# RSSI_Tag_V1.net
KiCad netlist of a schematic drawn in Altium Designer
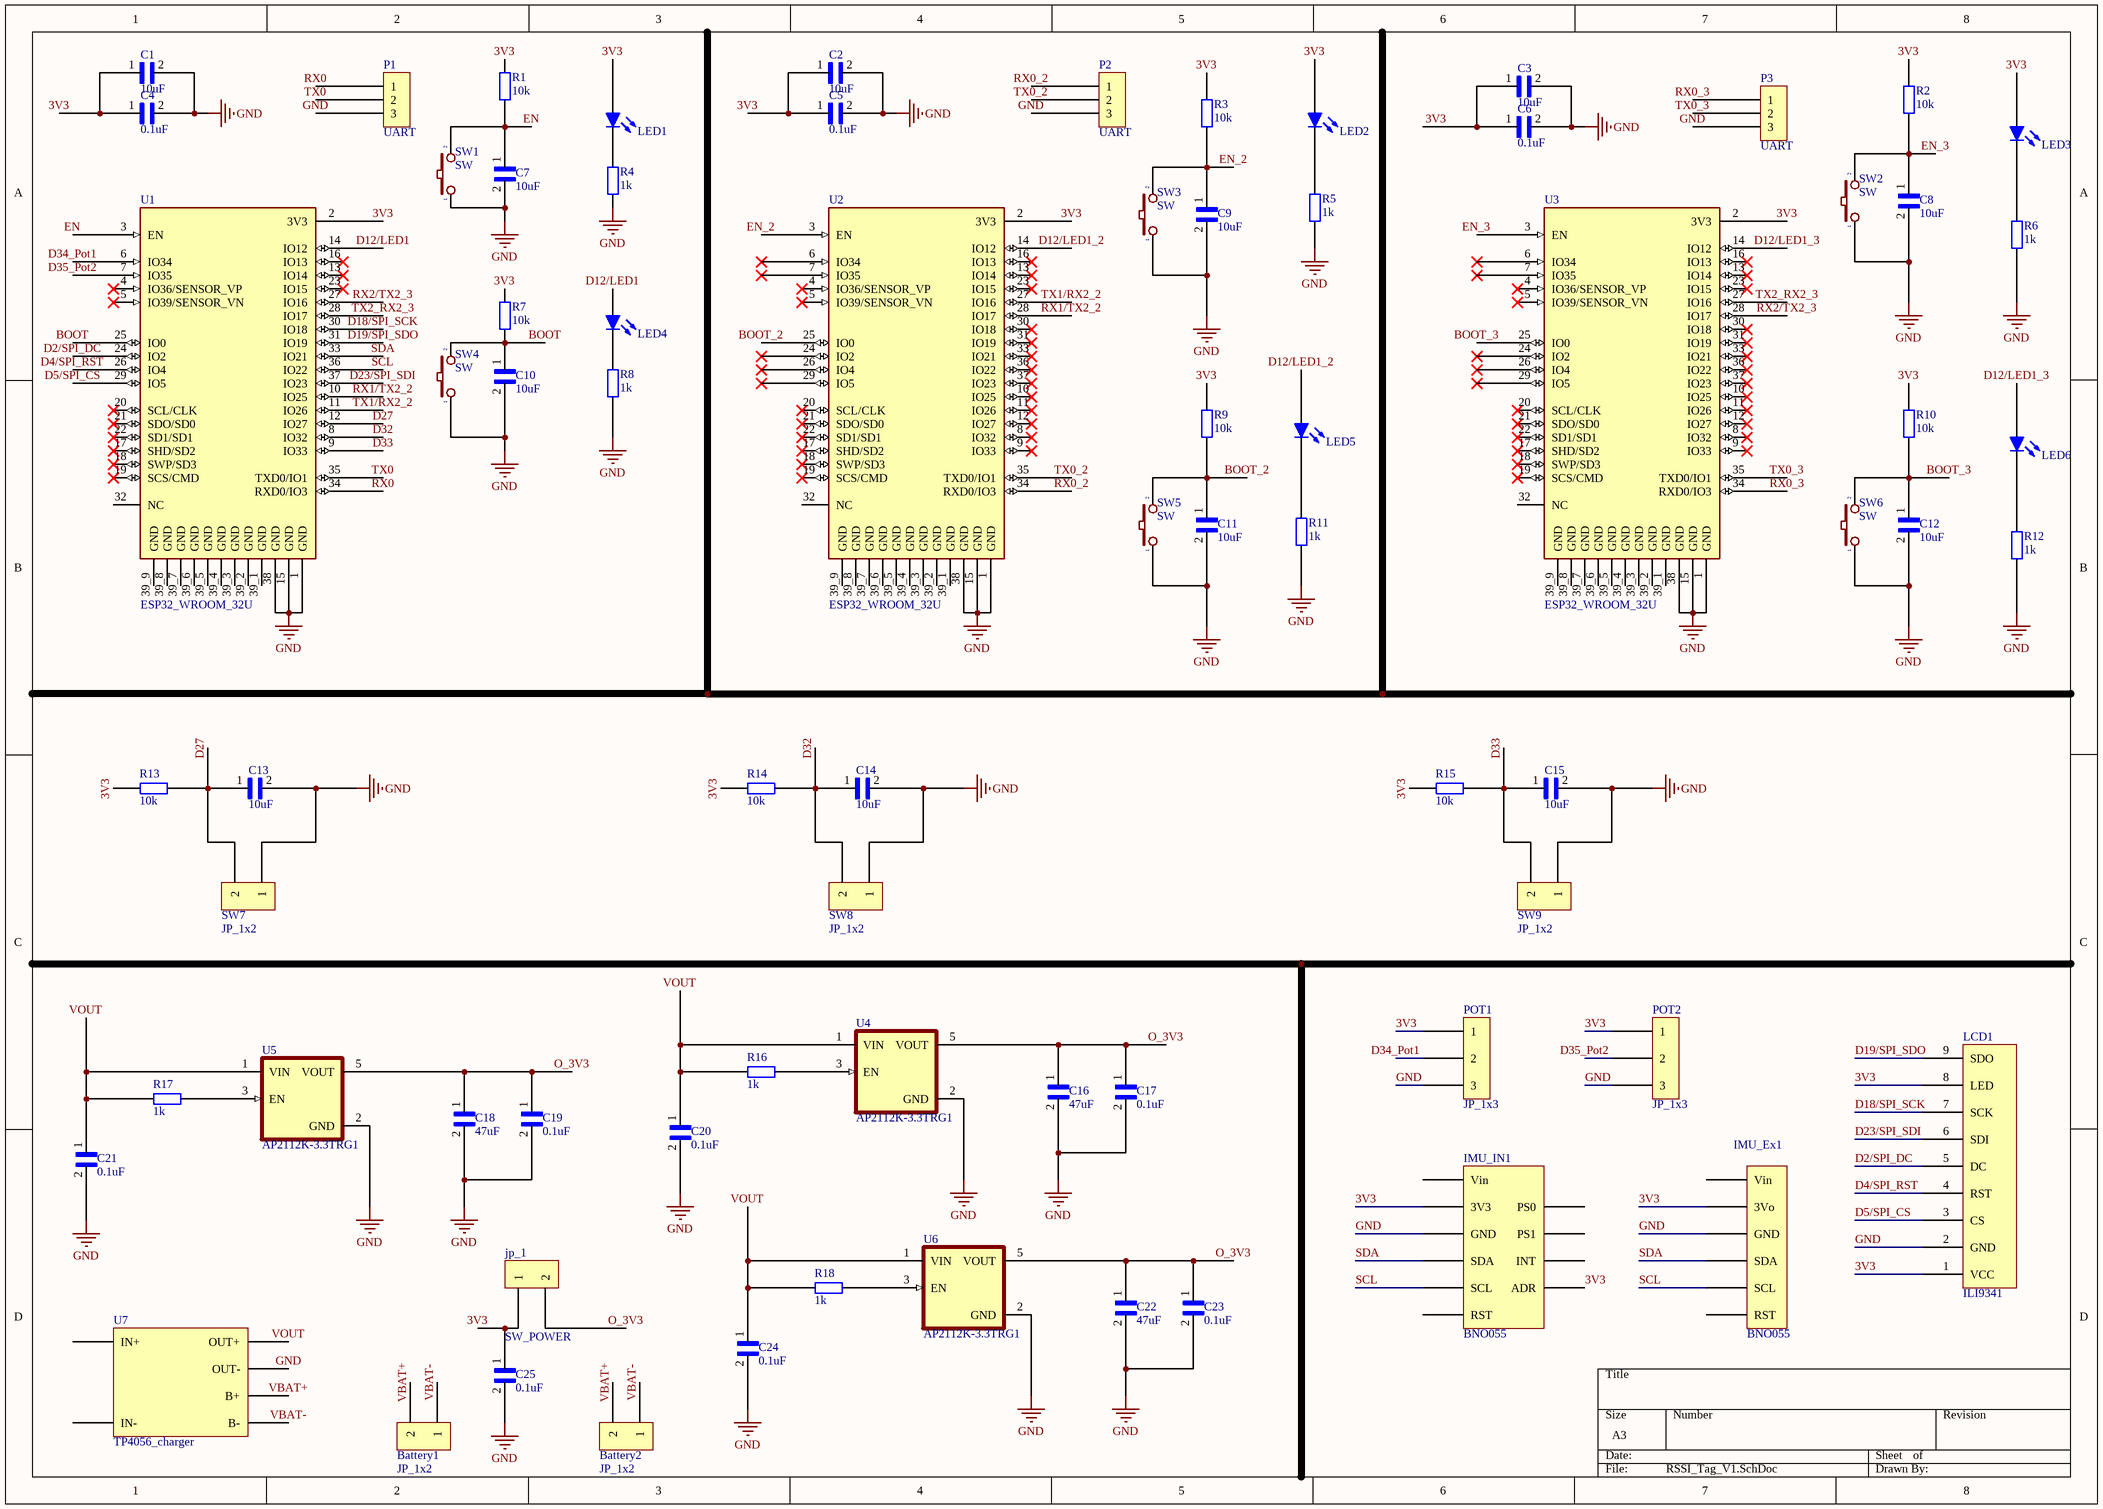
[diagram p0: RSSI_Tag_V1.SchDoc]

(export (version "E")
  (design (tool "Eeschema 10.0.6"))
  (components
    (comp (ref "Battery1")
      (value "JP_1x2")
      (footprint "JP_1x2")
      (libsource (lib "Target_tracking_20242v2") (part "JP_1x2"))
    )
    (comp (ref "Battery2")
      (value "JP_1x2")
      (footprint "JP_1x2")
      (libsource (lib "Target_tracking_20242v2") (part "JP_1x2"))
    )
    (comp (ref "C1")
      (value "10uF")
      (footprint "Capacitor_0805")
      (description "Capacitor; Ceramic; Cap; .220uF; Tol 10%; SMT; Vol-Rtg 50V; X7R; Tape And Reel")
      (libsource (lib "Target_tracking_20242v3") (part "Capacitor_0805"))
    )
    (comp (ref "C2")
      (value "10uF")
      (footprint "Capacitor_0805")
      (description "Capacitor; Ceramic; Cap; .220uF; Tol 10%; SMT; Vol-Rtg 50V; X7R; Tape And Reel")
      (libsource (lib "Target_tracking_20242v3") (part "Capacitor_0805"))
    )
    (comp (ref "C3")
      (value "10uF")
      (footprint "Capacitor_0805")
      (description "Capacitor; Ceramic; Cap; .220uF; Tol 10%; SMT; Vol-Rtg 50V; X7R; Tape And Reel")
      (libsource (lib "Target_tracking_20242v3") (part "Capacitor_0805"))
    )
    (comp (ref "C4")
      (value "0.1uF")
      (footprint "Capacitor_0805")
      (description "Capacitor; Ceramic; Cap; .220uF; Tol 10%; SMT; Vol-Rtg 50V; X7R; Tape And Reel")
      (libsource (lib "Target_tracking_20242v3") (part "Capacitor_0805"))
    )
    (comp (ref "C5")
      (value "0.1uF")
      (footprint "Capacitor_0805")
      (description "Capacitor; Ceramic; Cap; .220uF; Tol 10%; SMT; Vol-Rtg 50V; X7R; Tape And Reel")
      (libsource (lib "Target_tracking_20242v3") (part "Capacitor_0805"))
    )
    (comp (ref "C6")
      (value "0.1uF")
      (footprint "Capacitor_0805")
      (description "Capacitor; Ceramic; Cap; .220uF; Tol 10%; SMT; Vol-Rtg 50V; X7R; Tape And Reel")
      (libsource (lib "Target_tracking_20242v3") (part "Capacitor_0805"))
    )
    (comp (ref "C7")
      (value "10uF")
      (footprint "Capacitor_0805")
      (description "Capacitor; Ceramic; Cap; .220uF; Tol 10%; SMT; Vol-Rtg 50V; X7R; Tape And Reel")
      (libsource (lib "") (part "Capacitor_0805_1"))
    )
    (comp (ref "C8")
      (value "10uF")
      (footprint "Capacitor_0805")
      (description "Capacitor; Ceramic; Cap; .220uF; Tol 10%; SMT; Vol-Rtg 50V; X7R; Tape And Reel")
      (libsource (lib "") (part "Capacitor_0805_1"))
    )
    (comp (ref "C9")
      (value "10uF")
      (footprint "Capacitor_0805")
      (description "Capacitor; Ceramic; Cap; .220uF; Tol 10%; SMT; Vol-Rtg 50V; X7R; Tape And Reel")
      (libsource (lib "") (part "Capacitor_0805_1"))
    )
    (comp (ref "C10")
      (value "10uF")
      (footprint "Capacitor_0805")
      (description "Capacitor; Ceramic; Cap; .220uF; Tol 10%; SMT; Vol-Rtg 50V; X7R; Tape And Reel")
      (libsource (lib "") (part "Capacitor_0805_1"))
    )
    (comp (ref "C11")
      (value "10uF")
      (footprint "Capacitor_0805")
      (description "Capacitor; Ceramic; Cap; .220uF; Tol 10%; SMT; Vol-Rtg 50V; X7R; Tape And Reel")
      (libsource (lib "") (part "Capacitor_0805_1"))
    )
    (comp (ref "C12")
      (value "10uF")
      (footprint "Capacitor_0805")
      (description "Capacitor; Ceramic; Cap; .220uF; Tol 10%; SMT; Vol-Rtg 50V; X7R; Tape And Reel")
      (libsource (lib "") (part "Capacitor_0805_1"))
    )
    (comp (ref "C13")
      (value "10uF")
      (footprint "Capacitor_0805")
      (description "Capacitor; Ceramic; Cap; .220uF; Tol 10%; SMT; Vol-Rtg 50V; X7R; Tape And Reel")
      (libsource (lib "Target_tracking_20242v3") (part "Capacitor_0805"))
    )
    (comp (ref "C14")
      (value "10uF")
      (footprint "Capacitor_0805")
      (description "Capacitor; Ceramic; Cap; .220uF; Tol 10%; SMT; Vol-Rtg 50V; X7R; Tape And Reel")
      (libsource (lib "Target_tracking_20242v3") (part "Capacitor_0805"))
    )
    (comp (ref "C15")
      (value "10uF")
      (footprint "Capacitor_0805")
      (description "Capacitor; Ceramic; Cap; .220uF; Tol 10%; SMT; Vol-Rtg 50V; X7R; Tape And Reel")
      (libsource (lib "Target_tracking_20242v3") (part "Capacitor_0805"))
    )
    (comp (ref "C16")
      (value "47uF")
      (footprint "Capacitor_0805")
      (description "Capacitor; Ceramic; Cap; .220uF; Tol 10%; SMT; Vol-Rtg 50V; X7R; Tape And Reel")
      (libsource (lib "") (part "Capacitor_0805_1"))
    )
    (comp (ref "C17")
      (value "0.1uF")
      (footprint "Capacitor_0805")
      (description "Capacitor; Ceramic; Cap; .220uF; Tol 10%; SMT; Vol-Rtg 50V; X7R; Tape And Reel")
      (libsource (lib "") (part "Capacitor_0805_1"))
    )
    (comp (ref "C18")
      (value "47uF")
      (footprint "Capacitor_0805")
      (description "Capacitor; Ceramic; Cap; .220uF; Tol 10%; SMT; Vol-Rtg 50V; X7R; Tape And Reel")
      (libsource (lib "") (part "Capacitor_0805_1"))
    )
    (comp (ref "C19")
      (value "0.1uF")
      (footprint "Capacitor_0805")
      (description "Capacitor; Ceramic; Cap; .220uF; Tol 10%; SMT; Vol-Rtg 50V; X7R; Tape And Reel")
      (libsource (lib "") (part "Capacitor_0805_1"))
    )
    (comp (ref "C20")
      (value "0.1uF")
      (footprint "Capacitor_0805")
      (description "Capacitor; Ceramic; Cap; .220uF; Tol 10%; SMT; Vol-Rtg 50V; X7R; Tape And Reel")
      (libsource (lib "") (part "Capacitor_0805_1"))
    )
    (comp (ref "C21")
      (value "0.1uF")
      (footprint "Capacitor_0805")
      (description "Capacitor; Ceramic; Cap; .220uF; Tol 10%; SMT; Vol-Rtg 50V; X7R; Tape And Reel")
      (libsource (lib "") (part "Capacitor_0805_1"))
    )
    (comp (ref "C22")
      (value "47uF")
      (footprint "Capacitor_0805")
      (description "Capacitor; Ceramic; Cap; .220uF; Tol 10%; SMT; Vol-Rtg 50V; X7R; Tape And Reel")
      (libsource (lib "") (part "Capacitor_0805_1"))
    )
    (comp (ref "C23")
      (value "0.1uF")
      (footprint "Capacitor_0805")
      (description "Capacitor; Ceramic; Cap; .220uF; Tol 10%; SMT; Vol-Rtg 50V; X7R; Tape And Reel")
      (libsource (lib "") (part "Capacitor_0805_1"))
    )
    (comp (ref "C24")
      (value "0.1uF")
      (footprint "Capacitor_0805")
      (description "Capacitor; Ceramic; Cap; .220uF; Tol 10%; SMT; Vol-Rtg 50V; X7R; Tape And Reel")
      (libsource (lib "") (part "Capacitor_0805_1"))
    )
    (comp (ref "C25")
      (value "0.1uF")
      (footprint "Capacitor_0805")
      (description "Capacitor; Ceramic; Cap; .220uF; Tol 10%; SMT; Vol-Rtg 50V; X7R; Tape And Reel")
      (libsource (lib "") (part "Capacitor_0805_1"))
    )
    (comp (ref "IMU_Ex1")
      (value "BNO055")
      (footprint "BNO055_External")
      (libsource (lib "Target_tracking_20242v2") (part "BNO055_External"))
    )
    (comp (ref "IMU_IN1")
      (value "BNO055")
      (footprint "BNO055_Internal")
      (libsource (lib "Target_tracking_20242v3") (part "BNO055"))
    )
    (comp (ref "jp_1")
      (value "SW_POWER")
      (footprint "JP_1x2")
      (libsource (lib "Target_tracking_20242v3") (part "JP_1x2"))
    )
    (comp (ref "LCD1")
      (value "ILI9341")
      (footprint "ILI9341_LCD3.5")
      (libsource (lib "Target_tracking_20242v2") (part "ILI9341_LCD3.5"))
    )
    (comp (ref "LED1")
      (value "Led")
      (footprint "Led 0805 Blue")
      (description "Typical LED")
      (libsource (lib "Project_LoRa") (part "Led"))
    )
    (comp (ref "LED2")
      (value "Led")
      (footprint "Led 0805 Blue")
      (description "Typical LED")
      (libsource (lib "Project_LoRa") (part "Led"))
    )
    (comp (ref "LED3")
      (value "Led")
      (footprint "Led 0805 Blue")
      (description "Typical LED")
      (libsource (lib "Project_LoRa") (part "Led"))
    )
    (comp (ref "LED4")
      (value "Led")
      (footprint "Led 0805 Blue")
      (description "Typical LED")
      (libsource (lib "Project_LoRa") (part "Led"))
    )
    (comp (ref "LED5")
      (value "Led")
      (footprint "Led 0805 Blue")
      (description "Typical LED")
      (libsource (lib "Project_LoRa") (part "Led"))
    )
    (comp (ref "LED6")
      (value "Led")
      (footprint "Led 0805 Blue")
      (description "Typical LED")
      (libsource (lib "Project_LoRa") (part "Led"))
    )
    (comp (ref "P1")
      (value "UART")
      (footprint "HDR/Header/3/BOX")
      (description "Header, 3-Pin")
      (libsource (lib "Project_LoRa") (part "Header 3"))
    )
    (comp (ref "P2")
      (value "UART")
      (footprint "HDR/Header/3/BOX")
      (description "Header, 3-Pin")
      (libsource (lib "Project_LoRa") (part "Header 3"))
    )
    (comp (ref "P3")
      (value "UART")
      (footprint "HDR/Header/3/BOX")
      (description "Header, 3-Pin")
      (libsource (lib "Project_LoRa") (part "Header 3"))
    )
    (comp (ref "POT1")
      (value "JP_1x3")
      (footprint "JP_1x3")
      (libsource (lib "Target_tracking_20242v2") (part "JP_1x3"))
    )
    (comp (ref "POT2")
      (value "JP_1x3")
      (footprint "JP_1x3")
      (libsource (lib "Target_tracking_20242v2") (part "JP_1x3"))
    )
    (comp (ref "R1")
      (value "10k")
      (footprint "tro smd 0805")
      (description "Dán")
      (libsource (lib "Project_LoRa") (part "Tro 0805 1% 10k"))
    )
    (comp (ref "R2")
      (value "10k")
      (footprint "tro smd 0805")
      (description "Dán")
      (libsource (lib "Project_LoRa") (part "Tro 0805 1% 10k"))
    )
    (comp (ref "R3")
      (value "10k")
      (footprint "tro smd 0805")
      (description "Dán")
      (libsource (lib "Project_LoRa") (part "Tro 0805 1% 10k"))
    )
    (comp (ref "R4")
      (value "1k")
      (footprint "tro smd 0805")
      (description "Dán")
      (libsource (lib "Project_LoRa") (part "Tro 0805 1% 1k"))
    )
    (comp (ref "R5")
      (value "1k")
      (footprint "tro smd 0805")
      (description "Dán")
      (libsource (lib "Project_LoRa") (part "Tro 0805 1% 1k"))
    )
    (comp (ref "R6")
      (value "1k")
      (footprint "tro smd 0805")
      (description "Dán")
      (libsource (lib "Project_LoRa") (part "Tro 0805 1% 1k"))
    )
    (comp (ref "R7")
      (value "10k")
      (footprint "tro smd 0805")
      (description "Dán")
      (libsource (lib "Project_LoRa") (part "Tro 0805 1% 10k"))
    )
    (comp (ref "R8")
      (value "1k")
      (footprint "tro smd 0805")
      (description "Dán")
      (libsource (lib "Project_LoRa") (part "Tro 0805 1% 1k"))
    )
    (comp (ref "R9")
      (value "10k")
      (footprint "tro smd 0805")
      (description "Dán")
      (libsource (lib "Project_LoRa") (part "Tro 0805 1% 10k"))
    )
    (comp (ref "R10")
      (value "10k")
      (footprint "tro smd 0805")
      (description "Dán")
      (libsource (lib "Project_LoRa") (part "Tro 0805 1% 10k"))
    )
    (comp (ref "R11")
      (value "1k")
      (footprint "tro smd 0805")
      (description "Dán")
      (libsource (lib "Project_LoRa") (part "Tro 0805 1% 1k"))
    )
    (comp (ref "R12")
      (value "1k")
      (footprint "tro smd 0805")
      (description "Dán")
      (libsource (lib "Project_LoRa") (part "Tro 0805 1% 1k"))
    )
    (comp (ref "R13")
      (value "10k")
      (footprint "tro smd 0805")
      (description "Dán")
      (libsource (lib "Project_LoRa") (part "Tro 0805 1% 10k"))
    )
    (comp (ref "R14")
      (value "10k")
      (footprint "tro smd 0805")
      (description "Dán")
      (libsource (lib "Project_LoRa") (part "Tro 0805 1% 10k"))
    )
    (comp (ref "R15")
      (value "10k")
      (footprint "tro smd 0805")
      (description "Dán")
      (libsource (lib "Project_LoRa") (part "Tro 0805 1% 10k"))
    )
    (comp (ref "R16")
      (value "1k")
      (footprint "tro smd 0805")
      (description "Dán")
      (libsource (lib "Project_LoRa") (part "Tro 0805 1% 1k"))
    )
    (comp (ref "R17")
      (value "1k")
      (footprint "tro smd 0805")
      (description "Dán")
      (libsource (lib "Project_LoRa") (part "Tro 0805 1% 1k"))
    )
    (comp (ref "R18")
      (value "1k")
      (footprint "tro smd 0805")
      (description "Dán")
      (libsource (lib "Project_LoRa") (part "Tro 0805 1% 1k"))
    )
    (comp (ref "SW1")
      (value "SW")
      (footprint "SW1-SMD")
      (description "Switch button 2 pin")
      (libsource (lib "Project_LoRa") (part "SW2"))
    )
    (comp (ref "SW2")
      (value "SW")
      (footprint "SW1-SMD")
      (description "Switch button 2 pin")
      (libsource (lib "Project_LoRa") (part "SW2"))
    )
    (comp (ref "SW3")
      (value "SW")
      (footprint "SW1-SMD")
      (description "Switch button 2 pin")
      (libsource (lib "Project_LoRa") (part "SW2"))
    )
    (comp (ref "SW4")
      (value "SW")
      (footprint "SW1-SMD")
      (description "Switch button 2 pin")
      (libsource (lib "Project_LoRa") (part "SW2"))
    )
    (comp (ref "SW5")
      (value "SW")
      (footprint "SW1-SMD")
      (description "Switch button 2 pin")
      (libsource (lib "Project_LoRa") (part "SW2"))
    )
    (comp (ref "SW6")
      (value "SW")
      (footprint "SW1-SMD")
      (description "Switch button 2 pin")
      (libsource (lib "Project_LoRa") (part "SW2"))
    )
    (comp (ref "SW7")
      (value "JP_1x2")
      (footprint "JP_1x2")
      (libsource (lib "Target_tracking_20242v2") (part "JP_1x2"))
    )
    (comp (ref "SW8")
      (value "JP_1x2")
      (footprint "JP_1x2")
      (libsource (lib "Target_tracking_20242v2") (part "JP_1x2"))
    )
    (comp (ref "SW9")
      (value "JP_1x2")
      (footprint "JP_1x2")
      (libsource (lib "Target_tracking_20242v2") (part "JP_1x2"))
    )
    (comp (ref "U1")
      (value "ESP32_WROOM_32U")
      (footprint "ESP32_WROOM_32U")
      (libsource (lib "Target_tracking_20242v3") (part "ESP32_WROOM_32U"))
    )
    (comp (ref "U2")
      (value "ESP32_WROOM_32U")
      (footprint "ESP32_WROOM_32U")
      (libsource (lib "Target_tracking_20242v3") (part "ESP32_WROOM_32U"))
    )
    (comp (ref "U3")
      (value "ESP32_WROOM_32U")
      (footprint "ESP32_WROOM_32U")
      (libsource (lib "Target_tracking_20242v3") (part "ESP32_WROOM_32U"))
    )
    (comp (ref "U4")
      (value "AP2112K-3.3TRG1")
      (footprint "SOT95P285X140-5N")
      (description "Linear Voltage Regulator IC Positive Fixed 1 Output 600mA SOT-25")
      (fields (field (name "MF") "Diodes Inc."))
      (libsource (lib "Project_LoRa") (part "AP2112K-3.3TRG1"))
    )
    (comp (ref "U5")
      (value "AP2112K-3.3TRG1")
      (footprint "SOT95P285X140-5N")
      (description "Linear Voltage Regulator IC Positive Fixed 1 Output 600mA SOT-25")
      (fields (field (name "MF") "Diodes Inc."))
      (libsource (lib "Project_LoRa") (part "AP2112K-3.3TRG1"))
    )
    (comp (ref "U6")
      (value "AP2112K-3.3TRG1")
      (footprint "SOT95P285X140-5N")
      (description "Linear Voltage Regulator IC Positive Fixed 1 Output 600mA SOT-25")
      (fields (field (name "MF") "Diodes Inc."))
      (libsource (lib "Project_LoRa") (part "AP2112K-3.3TRG1"))
    )
    (comp (ref "U7")
      (value "TP4056_charger")
      (footprint "TP4056_charger")
      (libsource (lib "Target_tracking_20242v3") (part "TP4056_charger"))
    )
  )
  (nets
    (net (code "1") (name "/3V3") (class "Default")
      (node (ref "C1") (pin "1") (pinfunction "1_1") (pintype "passive"))
      (node (ref "C2") (pin "1") (pinfunction "1_1") (pintype "passive"))
      (node (ref "C25") (pin "1") (pinfunction "1_1") (pintype "passive"))
      (node (ref "C3") (pin "1") (pinfunction "1_1") (pintype "passive"))
      (node (ref "C4") (pin "1") (pinfunction "1_1") (pintype "passive"))
      (node (ref "C5") (pin "1") (pinfunction "1_1") (pintype "passive"))
      (node (ref "C6") (pin "1") (pinfunction "1_1") (pintype "passive"))
      (node (ref "IMU_Ex1") (pin "2") (pinfunction "3Vo_2") (pintype "passive"))
      (node (ref "IMU_IN1") (pin "2") (pinfunction "3V3_2") (pintype "passive"))
      (node (ref "IMU_IN1") (pin "7") (pinfunction "ADR_7") (pintype "passive"))
      (node (ref "LCD1") (pin "1") (pinfunction "VCC_1") (pintype "passive"))
      (node (ref "LCD1") (pin "8") (pinfunction "LED_8") (pintype "passive"))
      (node (ref "LED1") (pin "1") (pinfunction "A_1") (pintype "passive"))
      (node (ref "LED2") (pin "1") (pinfunction "A_1") (pintype "passive"))
      (node (ref "LED3") (pin "1") (pinfunction "A_1") (pintype "passive"))
      (node (ref "POT1") (pin "1") (pinfunction "1_1") (pintype "passive"))
      (node (ref "POT2") (pin "1") (pinfunction "1_1") (pintype "passive"))
      (node (ref "R1") (pin "2") (pinfunction "2_2") (pintype "passive"))
      (node (ref "R10") (pin "2") (pinfunction "2_2") (pintype "passive"))
      (node (ref "R13") (pin "2") (pinfunction "2_2") (pintype "passive"))
      (node (ref "R14") (pin "2") (pinfunction "2_2") (pintype "passive"))
      (node (ref "R15") (pin "2") (pinfunction "2_2") (pintype "passive"))
      (node (ref "R2") (pin "2") (pinfunction "2_2") (pintype "passive"))
      (node (ref "R3") (pin "2") (pinfunction "2_2") (pintype "passive"))
      (node (ref "R7") (pin "2") (pinfunction "2_2") (pintype "passive"))
      (node (ref "R9") (pin "2") (pinfunction "2_2") (pintype "passive"))
      (node (ref "U1") (pin "2") (pinfunction "3V3_2") (pintype "power_in"))
      (node (ref "U2") (pin "2") (pinfunction "3V3_2") (pintype "power_in"))
      (node (ref "U3") (pin "2") (pinfunction "3V3_2") (pintype "power_in"))
      (node (ref "jp_1") (pin "1") (pinfunction "1_1") (pintype "passive"))
    )
    (net (code "3") (name "/BOOT") (class "Default")
      (node (ref "C10") (pin "1") (pinfunction "1_1") (pintype "passive"))
      (node (ref "R7") (pin "1") (pinfunction "1_1") (pintype "passive"))
      (node (ref "SW4") (pin "2") (pinfunction "2_2") (pintype "passive"))
      (node (ref "U1") (pin "25") (pinfunction "IO0_25") (pintype "bidirectional"))
    )
    (net (code "4") (name "/BOOT_2") (class "Default")
      (node (ref "C11") (pin "1") (pinfunction "1_1") (pintype "passive"))
      (node (ref "R9") (pin "1") (pinfunction "1_1") (pintype "passive"))
      (node (ref "SW5") (pin "2") (pinfunction "2_2") (pintype "passive"))
      (node (ref "U2") (pin "25") (pinfunction "IO0_25") (pintype "bidirectional"))
    )
    (net (code "5") (name "/BOOT_3") (class "Default")
      (node (ref "C12") (pin "1") (pinfunction "1_1") (pintype "passive"))
      (node (ref "R10") (pin "1") (pinfunction "1_1") (pintype "passive"))
      (node (ref "SW6") (pin "2") (pinfunction "2_2") (pintype "passive"))
      (node (ref "U3") (pin "25") (pinfunction "IO0_25") (pintype "bidirectional"))
    )
    (net (code "6") (name "/D2{slash}SPI_DC") (class "Default")
      (node (ref "LCD1") (pin "5") (pinfunction "DC_5") (pintype "passive"))
      (node (ref "U1") (pin "24") (pinfunction "IO2_24") (pintype "bidirectional"))
    )
    (net (code "7") (name "/D4{slash}SPI_RST") (class "Default")
      (node (ref "LCD1") (pin "4") (pinfunction "RST_4") (pintype "passive"))
      (node (ref "U1") (pin "26") (pinfunction "IO4_26") (pintype "bidirectional"))
    )
    (net (code "8") (name "/D5{slash}SPI_CS") (class "Default")
      (node (ref "LCD1") (pin "3") (pinfunction "CS_3") (pintype "passive"))
      (node (ref "U1") (pin "29") (pinfunction "IO5_29") (pintype "bidirectional"))
    )
    (net (code "9") (name "/D12{slash}LED1") (class "Default")
      (node (ref "LED4") (pin "1") (pinfunction "A_1") (pintype "passive"))
      (node (ref "U1") (pin "14") (pinfunction "IO12_14") (pintype "bidirectional"))
    )
    (net (code "10") (name "/D12{slash}LED1_2") (class "Default")
      (node (ref "LED5") (pin "1") (pinfunction "A_1") (pintype "passive"))
      (node (ref "U2") (pin "14") (pinfunction "IO12_14") (pintype "bidirectional"))
    )
    (net (code "11") (name "/D12{slash}LED1_3") (class "Default")
      (node (ref "LED6") (pin "1") (pinfunction "A_1") (pintype "passive"))
      (node (ref "U3") (pin "14") (pinfunction "IO12_14") (pintype "bidirectional"))
    )
    (net (code "12") (name "/D18{slash}SPI_SCK") (class "Default")
      (node (ref "LCD1") (pin "7") (pinfunction "SCK_7") (pintype "passive"))
      (node (ref "U1") (pin "30") (pinfunction "IO18_30") (pintype "bidirectional"))
    )
    (net (code "13") (name "/D19{slash}SPI_SDO") (class "Default")
      (node (ref "LCD1") (pin "9") (pinfunction "SDO_9") (pintype "passive"))
      (node (ref "U1") (pin "31") (pinfunction "IO19_31") (pintype "bidirectional"))
    )
    (net (code "14") (name "/D23{slash}SPI_SDI") (class "Default")
      (node (ref "LCD1") (pin "6") (pinfunction "SDI_6") (pintype "passive"))
      (node (ref "U1") (pin "37") (pinfunction "IO23_37") (pintype "bidirectional"))
    )
    (net (code "15") (name "/D27") (class "Default")
      (node (ref "C13") (pin "1") (pinfunction "1_1") (pintype "passive"))
      (node (ref "R13") (pin "1") (pinfunction "1_1") (pintype "passive"))
      (node (ref "SW7") (pin "2") (pinfunction "2_2") (pintype "passive"))
      (node (ref "U1") (pin "12") (pinfunction "IO27_12") (pintype "bidirectional"))
    )
    (net (code "16") (name "/D32") (class "Default")
      (node (ref "C14") (pin "1") (pinfunction "1_1") (pintype "passive"))
      (node (ref "R14") (pin "1") (pinfunction "1_1") (pintype "passive"))
      (node (ref "SW8") (pin "2") (pinfunction "2_2") (pintype "passive"))
      (node (ref "U1") (pin "8") (pinfunction "IO32_8") (pintype "bidirectional"))
    )
    (net (code "17") (name "/D33") (class "Default")
      (node (ref "C15") (pin "1") (pinfunction "1_1") (pintype "passive"))
      (node (ref "R15") (pin "1") (pinfunction "1_1") (pintype "passive"))
      (node (ref "SW9") (pin "2") (pinfunction "2_2") (pintype "passive"))
      (node (ref "U1") (pin "9") (pinfunction "IO33_9") (pintype "bidirectional"))
    )
    (net (code "18") (name "/D34_Pot1") (class "Default")
      (node (ref "POT1") (pin "2") (pinfunction "2_2") (pintype "passive"))
      (node (ref "U1") (pin "6") (pinfunction "IO34_6") (pintype "input"))
    )
    (net (code "19") (name "/D35_Pot2") (class "Default")
      (node (ref "POT2") (pin "2") (pinfunction "2_2") (pintype "passive"))
      (node (ref "U1") (pin "7") (pinfunction "IO35_7") (pintype "input"))
    )
    (net (code "20") (name "/EN") (class "Default")
      (node (ref "C7") (pin "1") (pinfunction "1_1") (pintype "passive"))
      (node (ref "R1") (pin "1") (pinfunction "1_1") (pintype "passive"))
      (node (ref "SW1") (pin "2") (pinfunction "2_2") (pintype "passive"))
      (node (ref "U1") (pin "3") (pinfunction "EN_3") (pintype "input"))
    )
    (net (code "21") (name "/EN_2") (class "Default")
      (node (ref "C9") (pin "1") (pinfunction "1_1") (pintype "passive"))
      (node (ref "R3") (pin "1") (pinfunction "1_1") (pintype "passive"))
      (node (ref "SW3") (pin "2") (pinfunction "2_2") (pintype "passive"))
      (node (ref "U2") (pin "3") (pinfunction "EN_3") (pintype "input"))
    )
    (net (code "22") (name "/EN_3") (class "Default")
      (node (ref "C8") (pin "1") (pinfunction "1_1") (pintype "passive"))
      (node (ref "R2") (pin "1") (pinfunction "1_1") (pintype "passive"))
      (node (ref "SW2") (pin "2") (pinfunction "2_2") (pintype "passive"))
      (node (ref "U3") (pin "3") (pinfunction "EN_3") (pintype "input"))
    )
    (net (code "23") (name "/O_3V3") (class "Default")
      (node (ref "C16") (pin "1") (pinfunction "1_1") (pintype "passive"))
      (node (ref "C17") (pin "1") (pinfunction "1_1") (pintype "passive"))
      (node (ref "C18") (pin "1") (pinfunction "1_1") (pintype "passive"))
      (node (ref "C19") (pin "1") (pinfunction "1_1") (pintype "passive"))
      (node (ref "C22") (pin "1") (pinfunction "1_1") (pintype "passive"))
      (node (ref "C23") (pin "1") (pinfunction "1_1") (pintype "passive"))
      (node (ref "U4") (pin "5") (pinfunction "VOUT_5") (pintype "power_in"))
      (node (ref "U5") (pin "5") (pinfunction "VOUT_5") (pintype "power_in"))
      (node (ref "U6") (pin "5") (pinfunction "VOUT_5") (pintype "power_in"))
      (node (ref "jp_1") (pin "2") (pinfunction "2_2") (pintype "passive"))
    )
    (net (code "24") (name "/RX0") (class "Default")
      (node (ref "P1") (pin "1") (pinfunction "1_1") (pintype "passive"))
      (node (ref "U1") (pin "34") (pinfunction "RXD0/IO3_34") (pintype "bidirectional"))
    )
    (net (code "25") (name "/RX0_2") (class "Default")
      (node (ref "P2") (pin "1") (pinfunction "1_1") (pintype "passive"))
      (node (ref "U2") (pin "34") (pinfunction "RXD0/IO3_34") (pintype "bidirectional"))
    )
    (net (code "26") (name "/RX0_3") (class "Default")
      (node (ref "P3") (pin "1") (pinfunction "1_1") (pintype "passive"))
      (node (ref "U3") (pin "34") (pinfunction "RXD0/IO3_34") (pintype "bidirectional"))
    )
    (net (code "27") (name "/RX1{slash}TX2_2") (class "Default")
      (node (ref "U1") (pin "10") (pinfunction "IO25_10") (pintype "bidirectional"))
      (node (ref "U2") (pin "28") (pinfunction "IO17_28") (pintype "bidirectional"))
    )
    (net (code "28") (name "/RX2{slash}TX2_3") (class "Default")
      (node (ref "U1") (pin "27") (pinfunction "IO16_27") (pintype "bidirectional"))
      (node (ref "U3") (pin "28") (pinfunction "IO17_28") (pintype "bidirectional"))
    )
    (net (code "29") (name "/SCL") (class "Default")
      (node (ref "IMU_Ex1") (pin "5") (pinfunction "SCL_5") (pintype "passive"))
      (node (ref "IMU_IN1") (pin "5") (pinfunction "SCL_5") (pintype "passive"))
      (node (ref "U1") (pin "36") (pinfunction "IO22_36") (pintype "bidirectional"))
    )
    (net (code "30") (name "/SDA") (class "Default")
      (node (ref "IMU_Ex1") (pin "4") (pinfunction "SDA_4") (pintype "passive"))
      (node (ref "IMU_IN1") (pin "4") (pinfunction "SDA_4") (pintype "passive"))
      (node (ref "U1") (pin "33") (pinfunction "IO21_33") (pintype "bidirectional"))
    )
    (net (code "31") (name "/TX0") (class "Default")
      (node (ref "P1") (pin "2") (pinfunction "2_2") (pintype "passive"))
      (node (ref "U1") (pin "35") (pinfunction "TXD0/IO1_35") (pintype "bidirectional"))
    )
    (net (code "32") (name "/TX0_2") (class "Default")
      (node (ref "P2") (pin "2") (pinfunction "2_2") (pintype "passive"))
      (node (ref "U2") (pin "35") (pinfunction "TXD0/IO1_35") (pintype "bidirectional"))
    )
    (net (code "33") (name "/TX0_3") (class "Default")
      (node (ref "P3") (pin "2") (pinfunction "2_2") (pintype "passive"))
      (node (ref "U3") (pin "35") (pinfunction "TXD0/IO1_35") (pintype "bidirectional"))
    )
    (net (code "34") (name "/TX1{slash}RX2_2") (class "Default")
      (node (ref "U1") (pin "11") (pinfunction "IO26_11") (pintype "bidirectional"))
      (node (ref "U2") (pin "27") (pinfunction "IO16_27") (pintype "bidirectional"))
    )
    (net (code "35") (name "/TX2_RX2_3") (class "Default")
      (node (ref "U1") (pin "28") (pinfunction "IO17_28") (pintype "bidirectional"))
      (node (ref "U3") (pin "27") (pinfunction "IO16_27") (pintype "bidirectional"))
    )
    (net (code "36") (name "/VBAT+") (class "Default")
      (node (ref "Battery1") (pin "2") (pinfunction "2_2") (pintype "passive"))
      (node (ref "Battery2") (pin "2") (pinfunction "2_2") (pintype "passive"))
      (node (ref "U7") (pin "1") (pinfunction "B+_1") (pintype "passive"))
    )
    (net (code "37") (name "/VBAT-") (class "Default")
      (node (ref "Battery1") (pin "1") (pinfunction "1_1") (pintype "passive"))
      (node (ref "Battery2") (pin "1") (pinfunction "1_1") (pintype "passive"))
      (node (ref "U7") (pin "2") (pinfunction "B-_2") (pintype "passive"))
    )
    (net (code "38") (name "/VOUT") (class "Default")
      (node (ref "C20") (pin "1") (pinfunction "1_1") (pintype "passive"))
      (node (ref "C21") (pin "1") (pinfunction "1_1") (pintype "passive"))
      (node (ref "C24") (pin "1") (pinfunction "1_1") (pintype "passive"))
      (node (ref "R16") (pin "1") (pinfunction "1_1") (pintype "passive"))
      (node (ref "R17") (pin "1") (pinfunction "1_1") (pintype "passive"))
      (node (ref "R18") (pin "1") (pinfunction "1_1") (pintype "passive"))
      (node (ref "U4") (pin "1") (pinfunction "VIN_1") (pintype "power_in"))
      (node (ref "U5") (pin "1") (pinfunction "VIN_1") (pintype "power_in"))
      (node (ref "U6") (pin "1") (pinfunction "VIN_1") (pintype "power_in"))
      (node (ref "U7") (pin "3") (pinfunction "OUT+_3") (pintype "passive"))
    )
    (net (code "39") (name "GND") (class "Default")
      (node (ref "C1") (pin "2") (pinfunction "2_2") (pintype "passive"))
      (node (ref "C10") (pin "2") (pinfunction "2_2") (pintype "passive"))
      (node (ref "C11") (pin "2") (pinfunction "2_2") (pintype "passive"))
      (node (ref "C12") (pin "2") (pinfunction "2_2") (pintype "passive"))
      (node (ref "C13") (pin "2") (pinfunction "2_2") (pintype "passive"))
      (node (ref "C14") (pin "2") (pinfunction "2_2") (pintype "passive"))
      (node (ref "C15") (pin "2") (pinfunction "2_2") (pintype "passive"))
      (node (ref "C16") (pin "2") (pinfunction "2_2") (pintype "passive"))
      (node (ref "C17") (pin "2") (pinfunction "2_2") (pintype "passive"))
      (node (ref "C18") (pin "2") (pinfunction "2_2") (pintype "passive"))
      (node (ref "C19") (pin "2") (pinfunction "2_2") (pintype "passive"))
      (node (ref "C2") (pin "2") (pinfunction "2_2") (pintype "passive"))
      (node (ref "C20") (pin "2") (pinfunction "2_2") (pintype "passive"))
      (node (ref "C21") (pin "2") (pinfunction "2_2") (pintype "passive"))
      (node (ref "C22") (pin "2") (pinfunction "2_2") (pintype "passive"))
      (node (ref "C23") (pin "2") (pinfunction "2_2") (pintype "passive"))
      (node (ref "C24") (pin "2") (pinfunction "2_2") (pintype "passive"))
      (node (ref "C25") (pin "2") (pinfunction "2_2") (pintype "passive"))
      (node (ref "C3") (pin "2") (pinfunction "2_2") (pintype "passive"))
      (node (ref "C4") (pin "2") (pinfunction "2_2") (pintype "passive"))
      (node (ref "C5") (pin "2") (pinfunction "2_2") (pintype "passive"))
      (node (ref "C6") (pin "2") (pinfunction "2_2") (pintype "passive"))
      (node (ref "C7") (pin "2") (pinfunction "2_2") (pintype "passive"))
      (node (ref "C8") (pin "2") (pinfunction "2_2") (pintype "passive"))
      (node (ref "C9") (pin "2") (pinfunction "2_2") (pintype "passive"))
      (node (ref "IMU_Ex1") (pin "3") (pinfunction "GND_3") (pintype "passive"))
      (node (ref "IMU_IN1") (pin "3") (pinfunction "GND_3") (pintype "passive"))
      (node (ref "LCD1") (pin "2") (pinfunction "GND_2") (pintype "passive"))
      (node (ref "P1") (pin "3") (pinfunction "3_3") (pintype "passive"))
      (node (ref "P2") (pin "3") (pinfunction "3_3") (pintype "passive"))
      (node (ref "P3") (pin "3") (pinfunction "3_3") (pintype "passive"))
      (node (ref "POT1") (pin "3") (pinfunction "3_3") (pintype "passive"))
      (node (ref "POT2") (pin "3") (pinfunction "3_3") (pintype "passive"))
      (node (ref "R11") (pin "2") (pinfunction "2_2") (pintype "passive"))
      (node (ref "R12") (pin "2") (pinfunction "2_2") (pintype "passive"))
      (node (ref "R4") (pin "2") (pinfunction "2_2") (pintype "passive"))
      (node (ref "R5") (pin "2") (pinfunction "2_2") (pintype "passive"))
      (node (ref "R6") (pin "2") (pinfunction "2_2") (pintype "passive"))
      (node (ref "R8") (pin "2") (pinfunction "2_2") (pintype "passive"))
      (node (ref "SW1") (pin "1") (pinfunction "1_1") (pintype "passive"))
      (node (ref "SW2") (pin "1") (pinfunction "1_1") (pintype "passive"))
      (node (ref "SW3") (pin "1") (pinfunction "1_1") (pintype "passive"))
      (node (ref "SW4") (pin "1") (pinfunction "1_1") (pintype "passive"))
      (node (ref "SW5") (pin "1") (pinfunction "1_1") (pintype "passive"))
      (node (ref "SW6") (pin "1") (pinfunction "1_1") (pintype "passive"))
      (node (ref "SW7") (pin "1") (pinfunction "1_1") (pintype "passive"))
      (node (ref "SW8") (pin "1") (pinfunction "1_1") (pintype "passive"))
      (node (ref "SW9") (pin "1") (pinfunction "1_1") (pintype "passive"))
      (node (ref "U1") (pin "1") (pinfunction "GND_1") (pintype "power_in"))
      (node (ref "U1") (pin "15") (pinfunction "GND_15") (pintype "power_in"))
      (node (ref "U1") (pin "38") (pinfunction "GND_38") (pintype "power_in"))
      (node (ref "U2") (pin "1") (pinfunction "GND_1") (pintype "power_in"))
      (node (ref "U2") (pin "15") (pinfunction "GND_15") (pintype "power_in"))
      (node (ref "U2") (pin "38") (pinfunction "GND_38") (pintype "power_in"))
      (node (ref "U3") (pin "1") (pinfunction "GND_1") (pintype "power_in"))
      (node (ref "U3") (pin "15") (pinfunction "GND_15") (pintype "power_in"))
      (node (ref "U3") (pin "38") (pinfunction "GND_38") (pintype "power_in"))
      (node (ref "U4") (pin "2") (pinfunction "GND_2") (pintype "power_in"))
      (node (ref "U5") (pin "2") (pinfunction "GND_2") (pintype "power_in"))
      (node (ref "U6") (pin "2") (pinfunction "GND_2") (pintype "power_in"))
      (node (ref "U7") (pin "4") (pinfunction "OUT-_4") (pintype "passive"))
    )
    (net (code "40") (name "Net-(LED1-K)") (class "Default")
      (node (ref "LED1") (pin "2") (pinfunction "K_2") (pintype "passive"))
      (node (ref "R4") (pin "1") (pinfunction "1_1") (pintype "passive"))
    )
    (net (code "41") (name "Net-(LED2-K)") (class "Default")
      (node (ref "LED2") (pin "2") (pinfunction "K_2") (pintype "passive"))
      (node (ref "R5") (pin "1") (pinfunction "1_1") (pintype "passive"))
    )
    (net (code "42") (name "Net-(LED3-K)") (class "Default")
      (node (ref "LED3") (pin "2") (pinfunction "K_2") (pintype "passive"))
      (node (ref "R6") (pin "1") (pinfunction "1_1") (pintype "passive"))
    )
    (net (code "43") (name "Net-(LED4-K)") (class "Default")
      (node (ref "LED4") (pin "2") (pinfunction "K_2") (pintype "passive"))
      (node (ref "R8") (pin "1") (pinfunction "1_1") (pintype "passive"))
    )
    (net (code "44") (name "Net-(LED5-K)") (class "Default")
      (node (ref "LED5") (pin "2") (pinfunction "K_2") (pintype "passive"))
      (node (ref "R11") (pin "1") (pinfunction "1_1") (pintype "passive"))
    )
    (net (code "45") (name "Net-(LED6-K)") (class "Default")
      (node (ref "LED6") (pin "2") (pinfunction "K_2") (pintype "passive"))
      (node (ref "R12") (pin "1") (pinfunction "1_1") (pintype "passive"))
    )
    (net (code "46") (name "Net-(U4-EN)") (class "Default")
      (node (ref "R16") (pin "2") (pinfunction "2_2") (pintype "passive"))
      (node (ref "U4") (pin "3") (pinfunction "EN_3") (pintype "input"))
    )
    (net (code "47") (name "Net-(U5-EN)") (class "Default")
      (node (ref "R17") (pin "2") (pinfunction "2_2") (pintype "passive"))
      (node (ref "U5") (pin "3") (pinfunction "EN_3") (pintype "input"))
    )
    (net (code "48") (name "Net-(U6-EN)") (class "Default")
      (node (ref "R18") (pin "2") (pinfunction "2_2") (pintype "passive"))
      (node (ref "U6") (pin "3") (pinfunction "EN_3") (pintype "input"))
    )
    (net (code "49") (name "unconnected-(IMU_Ex1-RST-Pad6)") (class "Default")
      (node (ref "IMU_Ex1") (pin "6") (pinfunction "RST_6") (pintype "passive"))
    )
    (net (code "50") (name "unconnected-(IMU_Ex1-Vin-Pad1)") (class "Default")
      (node (ref "IMU_Ex1") (pin "1") (pinfunction "Vin_1") (pintype "passive"))
    )
    (net (code "51") (name "unconnected-(IMU_IN1-INT-Pad8)") (class "Default")
      (node (ref "IMU_IN1") (pin "8") (pinfunction "INT_8") (pintype "passive"))
    )
    (net (code "52") (name "unconnected-(IMU_IN1-PS0-Pad10)") (class "Default")
      (node (ref "IMU_IN1") (pin "10") (pinfunction "PS0_10") (pintype "passive"))
    )
    (net (code "53") (name "unconnected-(IMU_IN1-PS1-Pad9)") (class "Default")
      (node (ref "IMU_IN1") (pin "9") (pinfunction "PS1_9") (pintype "passive"))
    )
    (net (code "54") (name "unconnected-(IMU_IN1-RST-Pad6)") (class "Default")
      (node (ref "IMU_IN1") (pin "6") (pinfunction "RST_6") (pintype "passive"))
    )
    (net (code "55") (name "unconnected-(IMU_IN1-Vin-Pad1)") (class "Default")
      (node (ref "IMU_IN1") (pin "1") (pinfunction "Vin_1") (pintype "passive"))
    )
    (net (code "56") (name "unconnected-(U1-GND-Pad39_1)") (class "Default")
      (node (ref "U1") (pin "39_1") (pinfunction "GND_39_1") (pintype "power_in"))
    )
    (net (code "57") (name "unconnected-(U1-GND-Pad39_2)") (class "Default")
      (node (ref "U1") (pin "39_2") (pinfunction "GND_39_2") (pintype "power_in"))
    )
    (net (code "58") (name "unconnected-(U1-GND-Pad39_3)") (class "Default")
      (node (ref "U1") (pin "39_3") (pinfunction "GND_39_3") (pintype "power_in"))
    )
    (net (code "59") (name "unconnected-(U1-GND-Pad39_4)") (class "Default")
      (node (ref "U1") (pin "39_4") (pinfunction "GND_39_4") (pintype "power_in"))
    )
    (net (code "60") (name "unconnected-(U1-GND-Pad39_5)") (class "Default")
      (node (ref "U1") (pin "39_5") (pinfunction "GND_39_5") (pintype "power_in"))
    )
    (net (code "61") (name "unconnected-(U1-GND-Pad39_6)") (class "Default")
      (node (ref "U1") (pin "39_6") (pinfunction "GND_39_6") (pintype "power_in"))
    )
    (net (code "62") (name "unconnected-(U1-GND-Pad39_7)") (class "Default")
      (node (ref "U1") (pin "39_7") (pinfunction "GND_39_7") (pintype "power_in"))
    )
    (net (code "63") (name "unconnected-(U1-GND-Pad39_8)") (class "Default")
      (node (ref "U1") (pin "39_8") (pinfunction "GND_39_8") (pintype "power_in"))
    )
    (net (code "64") (name "unconnected-(U1-GND-Pad39_9)") (class "Default")
      (node (ref "U1") (pin "39_9") (pinfunction "GND_39_9") (pintype "power_in"))
    )
    (net (code "65") (name "unconnected-(U1-IO13-Pad16)") (class "Default")
      (node (ref "U1") (pin "16") (pinfunction "IO13_16") (pintype "bidirectional+no_connect"))
    )
    (net (code "66") (name "unconnected-(U1-IO14-Pad13)") (class "Default")
      (node (ref "U1") (pin "13") (pinfunction "IO14_13") (pintype "bidirectional+no_connect"))
    )
    (net (code "67") (name "unconnected-(U1-IO15-Pad23)") (class "Default")
      (node (ref "U1") (pin "23") (pinfunction "IO15_23") (pintype "bidirectional+no_connect"))
    )
    (net (code "68") (name "unconnected-(U1-IO36{slash}SENSOR_VP-Pad4)") (class "Default")
      (node (ref "U1") (pin "4") (pinfunction "IO36/SENSOR_VP_4") (pintype "input+no_connect"))
    )
    (net (code "69") (name "unconnected-(U1-IO39{slash}SENSOR_VN-Pad5)") (class "Default")
      (node (ref "U1") (pin "5") (pinfunction "IO39/SENSOR_VN_5") (pintype "input+no_connect"))
    )
    (net (code "70") (name "unconnected-(U1-NC-Pad32)") (class "Default")
      (node (ref "U1") (pin "32") (pinfunction "NC_32") (pintype "passive"))
    )
    (net (code "71") (name "unconnected-(U1-SCL{slash}CLK-Pad20)") (class "Default")
      (node (ref "U1") (pin "20") (pinfunction "SCL/CLK_20") (pintype "bidirectional+no_connect"))
    )
    (net (code "72") (name "unconnected-(U1-SCS{slash}CMD-Pad19)") (class "Default")
      (node (ref "U1") (pin "19") (pinfunction "SCS/CMD_19") (pintype "bidirectional+no_connect"))
    )
    (net (code "73") (name "unconnected-(U1-SD1{slash}SD1-Pad22)") (class "Default")
      (node (ref "U1") (pin "22") (pinfunction "SD1/SD1_22") (pintype "bidirectional+no_connect"))
    )
    (net (code "74") (name "unconnected-(U1-SDO{slash}SD0-Pad21)") (class "Default")
      (node (ref "U1") (pin "21") (pinfunction "SDO/SD0_21") (pintype "bidirectional+no_connect"))
    )
    (net (code "75") (name "unconnected-(U1-SHD{slash}SD2-Pad17)") (class "Default")
      (node (ref "U1") (pin "17") (pinfunction "SHD/SD2_17") (pintype "bidirectional+no_connect"))
    )
    (net (code "76") (name "unconnected-(U1-SWP{slash}SD3-Pad18)") (class "Default")
      (node (ref "U1") (pin "18") (pinfunction "SWP/SD3_18") (pintype "bidirectional+no_connect"))
    )
    (net (code "77") (name "unconnected-(U2-GND-Pad39_1)") (class "Default")
      (node (ref "U2") (pin "39_1") (pinfunction "GND_39_1") (pintype "power_in"))
    )
    (net (code "78") (name "unconnected-(U2-GND-Pad39_2)") (class "Default")
      (node (ref "U2") (pin "39_2") (pinfunction "GND_39_2") (pintype "power_in"))
    )
    (net (code "79") (name "unconnected-(U2-GND-Pad39_3)") (class "Default")
      (node (ref "U2") (pin "39_3") (pinfunction "GND_39_3") (pintype "power_in"))
    )
    (net (code "80") (name "unconnected-(U2-GND-Pad39_4)") (class "Default")
      (node (ref "U2") (pin "39_4") (pinfunction "GND_39_4") (pintype "power_in"))
    )
    (net (code "81") (name "unconnected-(U2-GND-Pad39_5)") (class "Default")
      (node (ref "U2") (pin "39_5") (pinfunction "GND_39_5") (pintype "power_in"))
    )
    (net (code "82") (name "unconnected-(U2-GND-Pad39_6)") (class "Default")
      (node (ref "U2") (pin "39_6") (pinfunction "GND_39_6") (pintype "power_in"))
    )
    (net (code "83") (name "unconnected-(U2-GND-Pad39_7)") (class "Default")
      (node (ref "U2") (pin "39_7") (pinfunction "GND_39_7") (pintype "power_in"))
    )
    (net (code "84") (name "unconnected-(U2-GND-Pad39_8)") (class "Default")
      (node (ref "U2") (pin "39_8") (pinfunction "GND_39_8") (pintype "power_in"))
    )
    (net (code "85") (name "unconnected-(U2-GND-Pad39_9)") (class "Default")
      (node (ref "U2") (pin "39_9") (pinfunction "GND_39_9") (pintype "power_in"))
    )
    (net (code "86") (name "unconnected-(U2-IO2-Pad24)") (class "Default")
      (node (ref "U2") (pin "24") (pinfunction "IO2_24") (pintype "bidirectional+no_connect"))
    )
    (net (code "87") (name "unconnected-(U2-IO4-Pad26)") (class "Default")
      (node (ref "U2") (pin "26") (pinfunction "IO4_26") (pintype "bidirectional+no_connect"))
    )
    (net (code "88") (name "unconnected-(U2-IO5-Pad29)") (class "Default")
      (node (ref "U2") (pin "29") (pinfunction "IO5_29") (pintype "bidirectional+no_connect"))
    )
    (net (code "89") (name "unconnected-(U2-IO13-Pad16)") (class "Default")
      (node (ref "U2") (pin "16") (pinfunction "IO13_16") (pintype "bidirectional+no_connect"))
    )
    (net (code "90") (name "unconnected-(U2-IO14-Pad13)") (class "Default")
      (node (ref "U2") (pin "13") (pinfunction "IO14_13") (pintype "bidirectional+no_connect"))
    )
    (net (code "91") (name "unconnected-(U2-IO15-Pad23)") (class "Default")
      (node (ref "U2") (pin "23") (pinfunction "IO15_23") (pintype "bidirectional+no_connect"))
    )
    (net (code "92") (name "unconnected-(U2-IO18-Pad30)") (class "Default")
      (node (ref "U2") (pin "30") (pinfunction "IO18_30") (pintype "bidirectional+no_connect"))
    )
    (net (code "93") (name "unconnected-(U2-IO19-Pad31)") (class "Default")
      (node (ref "U2") (pin "31") (pinfunction "IO19_31") (pintype "bidirectional+no_connect"))
    )
    (net (code "94") (name "unconnected-(U2-IO21-Pad33)") (class "Default")
      (node (ref "U2") (pin "33") (pinfunction "IO21_33") (pintype "bidirectional+no_connect"))
    )
    (net (code "95") (name "unconnected-(U2-IO22-Pad36)") (class "Default")
      (node (ref "U2") (pin "36") (pinfunction "IO22_36") (pintype "bidirectional+no_connect"))
    )
    (net (code "96") (name "unconnected-(U2-IO23-Pad37)") (class "Default")
      (node (ref "U2") (pin "37") (pinfunction "IO23_37") (pintype "bidirectional+no_connect"))
    )
    (net (code "97") (name "unconnected-(U2-IO25-Pad10)") (class "Default")
      (node (ref "U2") (pin "10") (pinfunction "IO25_10") (pintype "bidirectional+no_connect"))
    )
    (net (code "98") (name "unconnected-(U2-IO26-Pad11)") (class "Default")
      (node (ref "U2") (pin "11") (pinfunction "IO26_11") (pintype "bidirectional+no_connect"))
    )
    (net (code "99") (name "unconnected-(U2-IO27-Pad12)") (class "Default")
      (node (ref "U2") (pin "12") (pinfunction "IO27_12") (pintype "bidirectional+no_connect"))
    )
    (net (code "100") (name "unconnected-(U2-IO32-Pad8)") (class "Default")
      (node (ref "U2") (pin "8") (pinfunction "IO32_8") (pintype "bidirectional+no_connect"))
    )
    (net (code "101") (name "unconnected-(U2-IO33-Pad9)") (class "Default")
      (node (ref "U2") (pin "9") (pinfunction "IO33_9") (pintype "bidirectional+no_connect"))
    )
    (net (code "102") (name "unconnected-(U2-IO34-Pad6)") (class "Default")
      (node (ref "U2") (pin "6") (pinfunction "IO34_6") (pintype "input+no_connect"))
    )
    (net (code "103") (name "unconnected-(U2-IO35-Pad7)") (class "Default")
      (node (ref "U2") (pin "7") (pinfunction "IO35_7") (pintype "input+no_connect"))
    )
    (net (code "104") (name "unconnected-(U2-IO36{slash}SENSOR_VP-Pad4)") (class "Default")
      (node (ref "U2") (pin "4") (pinfunction "IO36/SENSOR_VP_4") (pintype "input+no_connect"))
    )
    (net (code "105") (name "unconnected-(U2-IO39{slash}SENSOR_VN-Pad5)") (class "Default")
      (node (ref "U2") (pin "5") (pinfunction "IO39/SENSOR_VN_5") (pintype "input+no_connect"))
    )
    (net (code "106") (name "unconnected-(U2-NC-Pad32)") (class "Default")
      (node (ref "U2") (pin "32") (pinfunction "NC_32") (pintype "passive"))
    )
    (net (code "107") (name "unconnected-(U2-SCL{slash}CLK-Pad20)") (class "Default")
      (node (ref "U2") (pin "20") (pinfunction "SCL/CLK_20") (pintype "bidirectional+no_connect"))
    )
    (net (code "108") (name "unconnected-(U2-SCS{slash}CMD-Pad19)") (class "Default")
      (node (ref "U2") (pin "19") (pinfunction "SCS/CMD_19") (pintype "bidirectional+no_connect"))
    )
    (net (code "109") (name "unconnected-(U2-SD1{slash}SD1-Pad22)") (class "Default")
      (node (ref "U2") (pin "22") (pinfunction "SD1/SD1_22") (pintype "bidirectional+no_connect"))
    )
    (net (code "110") (name "unconnected-(U2-SDO{slash}SD0-Pad21)") (class "Default")
      (node (ref "U2") (pin "21") (pinfunction "SDO/SD0_21") (pintype "bidirectional+no_connect"))
    )
    (net (code "111") (name "unconnected-(U2-SHD{slash}SD2-Pad17)") (class "Default")
      (node (ref "U2") (pin "17") (pinfunction "SHD/SD2_17") (pintype "bidirectional+no_connect"))
    )
    (net (code "112") (name "unconnected-(U2-SWP{slash}SD3-Pad18)") (class "Default")
      (node (ref "U2") (pin "18") (pinfunction "SWP/SD3_18") (pintype "bidirectional+no_connect"))
    )
    (net (code "113") (name "unconnected-(U3-GND-Pad39_1)") (class "Default")
      (node (ref "U3") (pin "39_1") (pinfunction "GND_39_1") (pintype "power_in"))
    )
    (net (code "114") (name "unconnected-(U3-GND-Pad39_2)") (class "Default")
      (node (ref "U3") (pin "39_2") (pinfunction "GND_39_2") (pintype "power_in"))
    )
    (net (code "115") (name "unconnected-(U3-GND-Pad39_3)") (class "Default")
      (node (ref "U3") (pin "39_3") (pinfunction "GND_39_3") (pintype "power_in"))
    )
    (net (code "116") (name "unconnected-(U3-GND-Pad39_4)") (class "Default")
      (node (ref "U3") (pin "39_4") (pinfunction "GND_39_4") (pintype "power_in"))
    )
    (net (code "117") (name "unconnected-(U3-GND-Pad39_5)") (class "Default")
      (node (ref "U3") (pin "39_5") (pinfunction "GND_39_5") (pintype "power_in"))
    )
    (net (code "118") (name "unconnected-(U3-GND-Pad39_6)") (class "Default")
      (node (ref "U3") (pin "39_6") (pinfunction "GND_39_6") (pintype "power_in"))
    )
    (net (code "119") (name "unconnected-(U3-GND-Pad39_7)") (class "Default")
      (node (ref "U3") (pin "39_7") (pinfunction "GND_39_7") (pintype "power_in"))
    )
    (net (code "120") (name "unconnected-(U3-GND-Pad39_8)") (class "Default")
      (node (ref "U3") (pin "39_8") (pinfunction "GND_39_8") (pintype "power_in"))
    )
    (net (code "121") (name "unconnected-(U3-GND-Pad39_9)") (class "Default")
      (node (ref "U3") (pin "39_9") (pinfunction "GND_39_9") (pintype "power_in"))
    )
    (net (code "122") (name "unconnected-(U3-IO2-Pad24)") (class "Default")
      (node (ref "U3") (pin "24") (pinfunction "IO2_24") (pintype "bidirectional+no_connect"))
    )
    (net (code "123") (name "unconnected-(U3-IO4-Pad26)") (class "Default")
      (node (ref "U3") (pin "26") (pinfunction "IO4_26") (pintype "bidirectional+no_connect"))
    )
    (net (code "124") (name "unconnected-(U3-IO5-Pad29)") (class "Default")
      (node (ref "U3") (pin "29") (pinfunction "IO5_29") (pintype "bidirectional+no_connect"))
    )
    (net (code "125") (name "unconnected-(U3-IO13-Pad16)") (class "Default")
      (node (ref "U3") (pin "16") (pinfunction "IO13_16") (pintype "bidirectional+no_connect"))
    )
    (net (code "126") (name "unconnected-(U3-IO14-Pad13)") (class "Default")
      (node (ref "U3") (pin "13") (pinfunction "IO14_13") (pintype "bidirectional+no_connect"))
    )
    (net (code "127") (name "unconnected-(U3-IO15-Pad23)") (class "Default")
      (node (ref "U3") (pin "23") (pinfunction "IO15_23") (pintype "bidirectional+no_connect"))
    )
    (net (code "128") (name "unconnected-(U3-IO18-Pad30)") (class "Default")
      (node (ref "U3") (pin "30") (pinfunction "IO18_30") (pintype "bidirectional+no_connect"))
    )
    (net (code "129") (name "unconnected-(U3-IO19-Pad31)") (class "Default")
      (node (ref "U3") (pin "31") (pinfunction "IO19_31") (pintype "bidirectional+no_connect"))
    )
    (net (code "130") (name "unconnected-(U3-IO21-Pad33)") (class "Default")
      (node (ref "U3") (pin "33") (pinfunction "IO21_33") (pintype "bidirectional+no_connect"))
    )
    (net (code "131") (name "unconnected-(U3-IO22-Pad36)") (class "Default")
      (node (ref "U3") (pin "36") (pinfunction "IO22_36") (pintype "bidirectional+no_connect"))
    )
    (net (code "132") (name "unconnected-(U3-IO23-Pad37)") (class "Default")
      (node (ref "U3") (pin "37") (pinfunction "IO23_37") (pintype "bidirectional+no_connect"))
    )
    (net (code "133") (name "unconnected-(U3-IO25-Pad10)") (class "Default")
      (node (ref "U3") (pin "10") (pinfunction "IO25_10") (pintype "bidirectional+no_connect"))
    )
    (net (code "134") (name "unconnected-(U3-IO26-Pad11)") (class "Default")
      (node (ref "U3") (pin "11") (pinfunction "IO26_11") (pintype "bidirectional+no_connect"))
    )
    (net (code "135") (name "unconnected-(U3-IO27-Pad12)") (class "Default")
      (node (ref "U3") (pin "12") (pinfunction "IO27_12") (pintype "bidirectional+no_connect"))
    )
    (net (code "136") (name "unconnected-(U3-IO32-Pad8)") (class "Default")
      (node (ref "U3") (pin "8") (pinfunction "IO32_8") (pintype "bidirectional+no_connect"))
    )
    (net (code "137") (name "unconnected-(U3-IO33-Pad9)") (class "Default")
      (node (ref "U3") (pin "9") (pinfunction "IO33_9") (pintype "bidirectional+no_connect"))
    )
    (net (code "138") (name "unconnected-(U3-IO34-Pad6)") (class "Default")
      (node (ref "U3") (pin "6") (pinfunction "IO34_6") (pintype "input+no_connect"))
    )
    (net (code "139") (name "unconnected-(U3-IO35-Pad7)") (class "Default")
      (node (ref "U3") (pin "7") (pinfunction "IO35_7") (pintype "input+no_connect"))
    )
    (net (code "140") (name "unconnected-(U3-IO36{slash}SENSOR_VP-Pad4)") (class "Default")
      (node (ref "U3") (pin "4") (pinfunction "IO36/SENSOR_VP_4") (pintype "input+no_connect"))
    )
    (net (code "141") (name "unconnected-(U3-IO39{slash}SENSOR_VN-Pad5)") (class "Default")
      (node (ref "U3") (pin "5") (pinfunction "IO39/SENSOR_VN_5") (pintype "input+no_connect"))
    )
    (net (code "142") (name "unconnected-(U3-NC-Pad32)") (class "Default")
      (node (ref "U3") (pin "32") (pinfunction "NC_32") (pintype "passive"))
    )
    (net (code "143") (name "unconnected-(U3-SCL{slash}CLK-Pad20)") (class "Default")
      (node (ref "U3") (pin "20") (pinfunction "SCL/CLK_20") (pintype "bidirectional+no_connect"))
    )
    (net (code "144") (name "unconnected-(U3-SCS{slash}CMD-Pad19)") (class "Default")
      (node (ref "U3") (pin "19") (pinfunction "SCS/CMD_19") (pintype "bidirectional+no_connect"))
    )
    (net (code "145") (name "unconnected-(U3-SD1{slash}SD1-Pad22)") (class "Default")
      (node (ref "U3") (pin "22") (pinfunction "SD1/SD1_22") (pintype "bidirectional+no_connect"))
    )
    (net (code "146") (name "unconnected-(U3-SDO{slash}SD0-Pad21)") (class "Default")
      (node (ref "U3") (pin "21") (pinfunction "SDO/SD0_21") (pintype "bidirectional+no_connect"))
    )
    (net (code "147") (name "unconnected-(U3-SHD{slash}SD2-Pad17)") (class "Default")
      (node (ref "U3") (pin "17") (pinfunction "SHD/SD2_17") (pintype "bidirectional+no_connect"))
    )
    (net (code "148") (name "unconnected-(U3-SWP{slash}SD3-Pad18)") (class "Default")
      (node (ref "U3") (pin "18") (pinfunction "SWP/SD3_18") (pintype "bidirectional+no_connect"))
    )
    (net (code "149") (name "unconnected-(U7-IN+-Pad5)") (class "Default")
      (node (ref "U7") (pin "5") (pinfunction "IN+_5") (pintype "passive"))
    )
    (net (code "150") (name "unconnected-(U7-IN--Pad6)") (class "Default")
      (node (ref "U7") (pin "6") (pinfunction "IN-_6") (pintype "passive"))
    )
  )
)
